# power.net
KiCad netlist of a schematic drawn in Altium Designer
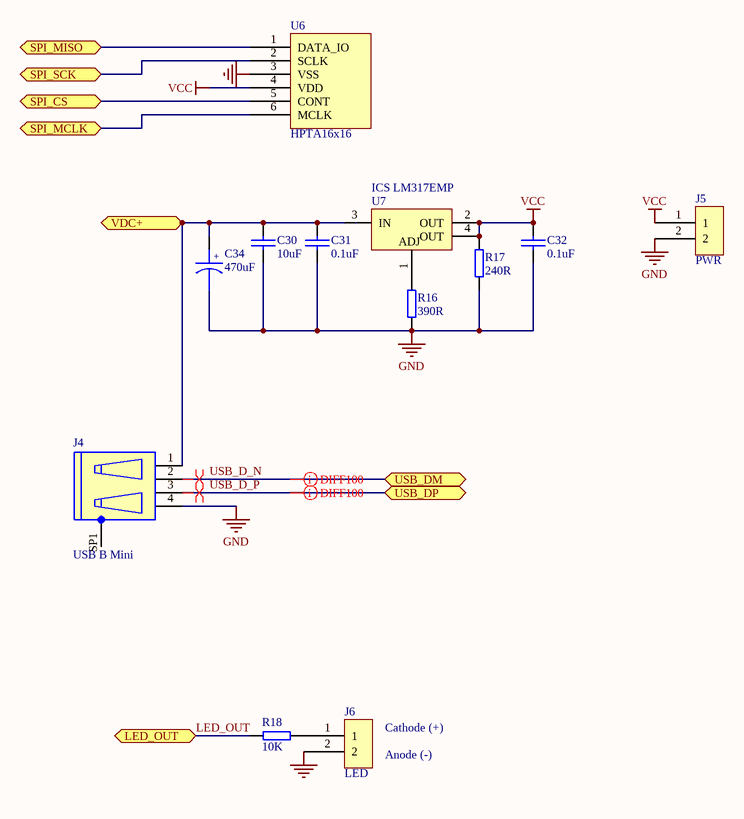
[diagram p0: power.SchDoc]

(export (version "E")
  (design (tool "Eeschema 10.0.6"))
  (components
    (comp (ref "C30")
      (value "10uF")
      (footprint "0603-IPC")
      (description "0.01uF 50V")
      (libsource (lib "NAUTECH SCHEMATIC") (part "CAP 0603 XXX"))
    )
    (comp (ref "C31")
      (value "0.1uF")
      (footprint "0603-IPC")
      (description "0.01uF 50V")
      (libsource (lib "NAUTECH SCHEMATIC") (part "CAP 0603 XXX"))
    )
    (comp (ref "C32")
      (value "0.1uF")
      (footprint "0603-IPC")
      (description "0.01uF 50V")
      (libsource (lib "NAUTECH SCHEMATIC") (part "CAP 0603 XXX"))
    )
    (comp (ref "C34")
      (value "470uF")
      (footprint "Cap G13")
      (description "220F 35V")
      (libsource (lib "corporatecam") (part "CAP SEL226 35"))
    )
    (comp (ref "J4")
      (value "USB B Mini")
      (footprint "USB MINI B - 5PIN")
      (description "USB Mini Connector RA 5 Pin")
      (fields (field (name "MANUFACTURER") "FCI"))
      (libsource (lib "Schlib1") (part "CON USB Mini B"))
    )
    (comp (ref "J5")
      (value "PWR")
      (footprint "HDR1X2")
      (description "2 Way Header")
      (libsource (lib "corporatecam") (part "2 Way Header 2.54mm"))
    )
    (comp (ref "J6")
      (value "LED")
      (footprint "HDR1X2")
      (description "2 Way Header")
      (libsource (lib "corporatecam") (part "2 Way Header 2.54mm"))
    )
    (comp (ref "R16")
      (value "390R")
      (footprint "0603-IPC")
      (description "RES1206")
      (libsource (lib "") (part "RES 0603 XXX_1"))
    )
    (comp (ref "R17")
      (value "240R")
      (footprint "0603-IPC")
      (description "RES1206")
      (libsource (lib "") (part "RES 0603 XXX_1"))
    )
    (comp (ref "R18")
      (value "10K")
      (footprint "0603-IPC")
      (description "RES0603")
      (libsource (lib "NAUTECH SCHEMATIC") (part "RES 0603 XXX"))
    )
    (comp (ref "U6")
      (value "HPTA16x16")
      (footprint "HTPA16x16")
      (libsource (lib "corporatecam") (part "HPTA16x16"))
    )
    (comp (ref "U7")
      (value "ICS LM317EMP")
      (footprint "SOT-223")
      (description "SOT223 Package, 1 Amp")
      (libsource (lib "corporatecam") (part "ICS LM317EMP"))
    )
  )
  (nets
    (net (code "1") (name "/LED_OUT") (class "Default")
      (node (ref "R18") (pin "2") (pinfunction "2_2") (pintype "passive"))
    )
    (net (code "2") (name "/SPI_CS") (class "Default")
      (node (ref "U6") (pin "5") (pinfunction "CONT_5") (pintype "passive"))
    )
    (net (code "3") (name "/SPI_MCLK") (class "Default")
      (node (ref "U6") (pin "6") (pinfunction "MCLK_6") (pintype "passive"))
    )
    (net (code "4") (name "/SPI_MISO") (class "Default")
      (node (ref "U6") (pin "1") (pinfunction "DATA_IO_1") (pintype "passive"))
    )
    (net (code "5") (name "/SPI_SCK") (class "Default")
      (node (ref "U6") (pin "2") (pinfunction "SCLK_2") (pintype "passive"))
    )
    (net (code "6") (name "/USB_D_N") (class "Default")
      (node (ref "J4") (pin "2") (pinfunction "DAT1_2") (pintype "passive"))
    )
    (net (code "7") (name "/USB_D_P") (class "Default")
      (node (ref "J4") (pin "3") (pinfunction "DAT2_3") (pintype "passive"))
    )
    (net (code "8") (name "/VDC+") (class "Default")
      (node (ref "C30") (pin "1") (pintype "passive"))
      (node (ref "C31") (pin "1") (pintype "passive"))
      (node (ref "C34") (pin "1") (pinfunction "1_1") (pintype "passive"))
      (node (ref "J4") (pin "1") (pinfunction "VBus_1") (pintype "passive"))
      (node (ref "U7") (pin "3") (pinfunction "IN_3") (pintype "passive"))
    )
    (net (code "9") (name "GND") (class "Default")
      (node (ref "C30") (pin "2") (pintype "passive"))
      (node (ref "C31") (pin "2") (pintype "passive"))
      (node (ref "C32") (pin "2") (pintype "passive"))
      (node (ref "C34") (pin "2") (pinfunction "2_2") (pintype "passive"))
      (node (ref "J4") (pin "4") (pinfunction "GND_4") (pintype "passive"))
      (node (ref "J5") (pin "2") (pinfunction "2_2") (pintype "power_in"))
      (node (ref "J6") (pin "2") (pinfunction "2_2") (pintype "power_in"))
      (node (ref "R16") (pin "1") (pinfunction "1_1") (pintype "passive"))
      (node (ref "R17") (pin "1") (pinfunction "1_1") (pintype "passive"))
      (node (ref "U6") (pin "3") (pinfunction "VSS_3") (pintype "passive"))
    )
    (net (code "10") (name "Net-(J6-Pad1)") (class "Default")
      (node (ref "J6") (pin "1") (pinfunction "1_1") (pintype "passive"))
      (node (ref "R18") (pin "1") (pinfunction "1_1") (pintype "passive"))
    )
    (net (code "11") (name "Net-(U7-ADJ)") (class "Default")
      (node (ref "R16") (pin "2") (pinfunction "2_2") (pintype "passive"))
      (node (ref "U7") (pin "1") (pinfunction "ADJ_1") (pintype "passive"))
    )
    (net (code "12") (name "VCC") (class "Default")
      (node (ref "C32") (pin "1") (pintype "passive"))
      (node (ref "J5") (pin "1") (pinfunction "1_1") (pintype "passive"))
      (node (ref "R17") (pin "2") (pinfunction "2_2") (pintype "passive"))
      (node (ref "U6") (pin "4") (pinfunction "VDD_4") (pintype "passive"))
      (node (ref "U7") (pin "2") (pinfunction "OUT_2") (pintype "passive"))
      (node (ref "U7") (pin "4") (pinfunction "OUT_4") (pintype "passive"))
    )
    (net (code "13") (name "unconnected-(J4-Not_Connected_Pin-PadNC)") (class "Default")
      (node (ref "J4") (pin "NC") (pinfunction "Not_Connected_Pin_NC") (pintype "passive"))
    )
    (net (code "14") (name "unconnected-(J4-Shield-PadSP1)") (class "Default")
      (node (ref "J4") (pin "SP1") (pinfunction "Shield_SP1") (pintype "passive"))
    )
  )
)
